# Controlador_de_velocidad_-_Placa_fuente_.net
KiCad netlist of a schematic drawn in Altium Designer
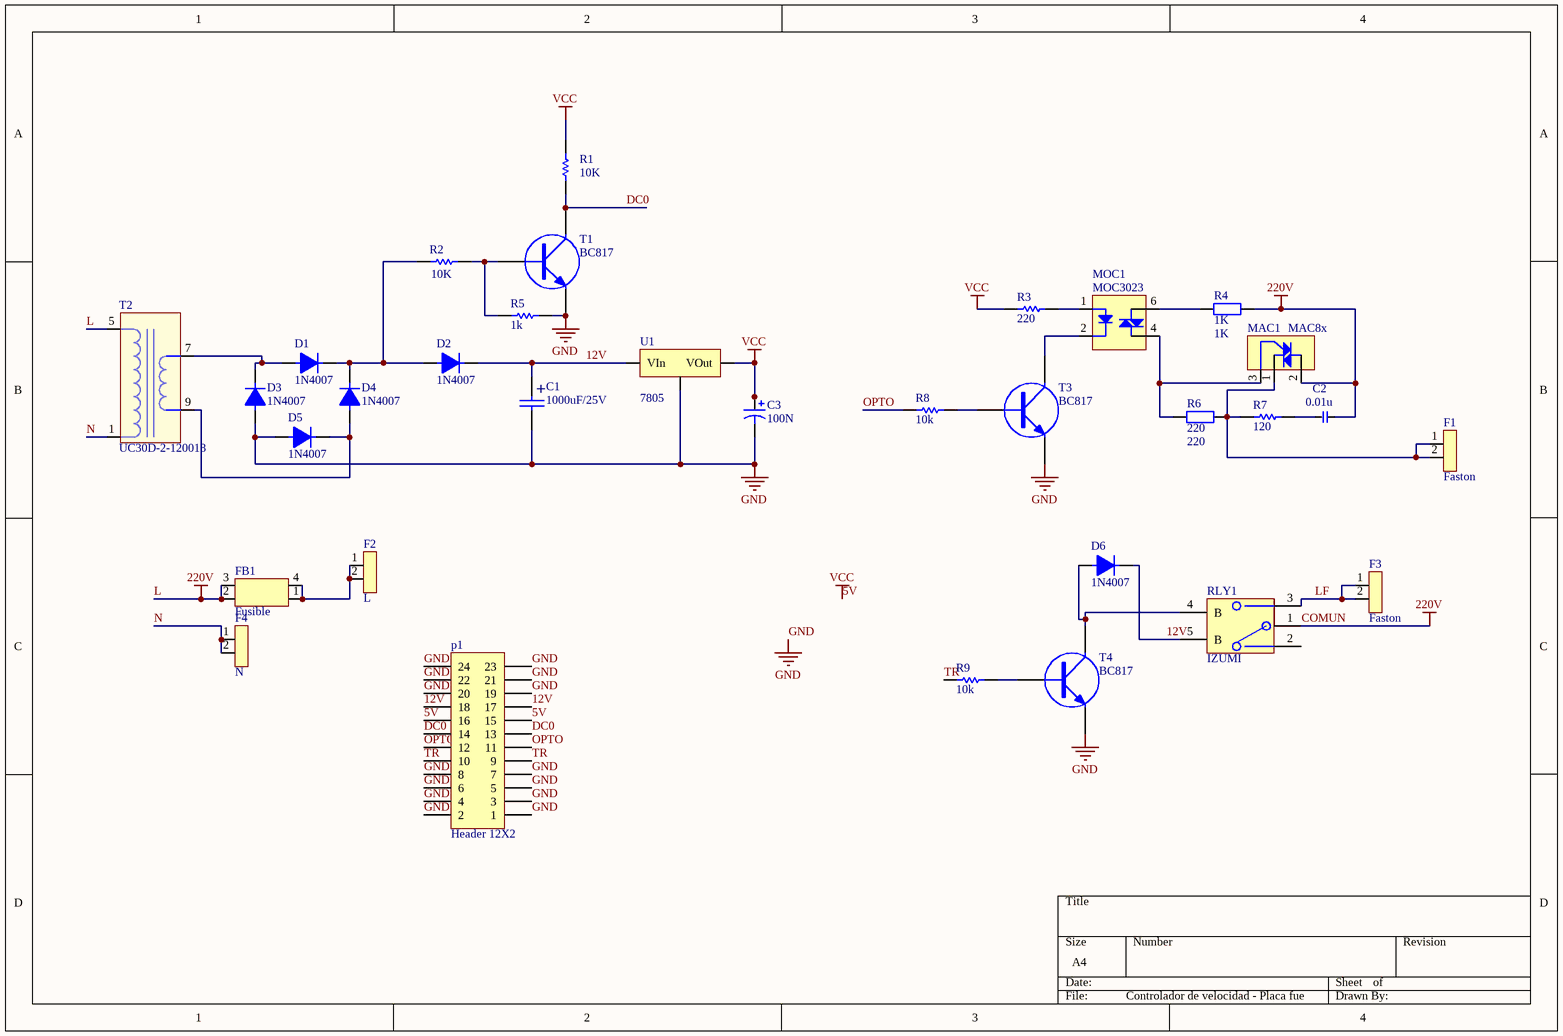
[diagram p0: Controlador de velocidad - Placa fuente v2.SchDoc]

(export (version "E")
  (design (tool "Eeschema 10.0.6"))
  (components
    (comp (ref "C1") (value "1000uF/25V") (footprint "CAP300RP") (libsource (lib "LIBPIOIX") (part "CAPPOL")))
    (comp (ref "C2")
      (value "0.01u")
      (footprint "AXIAL-0.4")
      (libsource (lib "Integrated_Lib_1") (part "CAP_MINI_NPOL"))
    )
    (comp (ref "C3")
      (value "100N")
      (footprint "C0805")
      (description "Polarized Capacitor (Surface Mount)")
      (fields (field (name "PUBLISHER") "Altium Limited"))
      (libsource (lib "Miscellaneous Devices") (part "Cap Pol3"))
    )
    (comp (ref "D1") (value "1N4007") (footprint "DO41") (libsource (lib "LIBPIOIX 0314A") (part "DIODO")))
    (comp (ref "D2") (value "1N4007") (footprint "DO41") (libsource (lib "LIBPIOIX 0314A") (part "DIODO")))
    (comp (ref "D3") (value "1N4007") (footprint "DO41") (libsource (lib "LIBPIOIX 0314A") (part "DIODO")))
    (comp (ref "D4") (value "1N4007") (footprint "DO41") (libsource (lib "LIBPIOIX 0314A") (part "DIODO")))
    (comp (ref "D5") (value "1N4007") (footprint "DO41") (libsource (lib "LIBPIOIX 0314A") (part "DIODO")))
    (comp (ref "D6") (value "1N4007") (footprint "DO41") (libsource (lib "LIBPIOIX 0314A") (part "DIODO")))
    (comp (ref "F1")
      (value "Faston")
      (footprint "Faston_V")
      (libsource (lib "Integrated_Library1") (part "FastonX1"))
    )
    (comp (ref "F2")
      (value "L")
      (footprint "Faston_V")
      (libsource (lib "Integrated_Library1") (part "FastonX1"))
    )
    (comp (ref "F3")
      (value "Faston")
      (footprint "Faston_V")
      (libsource (lib "Integrated_Library1") (part "FastonX1"))
    )
    (comp (ref "F4")
      (value "N")
      (footprint "Faston_V")
      (libsource (lib "Integrated_Library1") (part "FastonX1"))
    )
    (comp (ref "FB1")
      (value "Fusible")
      (footprint "Porta_fuse_2")
      (libsource (lib "Integrated_Library1") (part "Porta_fuse_1"))
    )
    (comp (ref "MAC1")
      (value "MAC8x")
      (footprint "TO-220_vert")
      (libsource (lib "Integrated_Library1") (part "MAC8x"))
    )
    (comp (ref "MOC1")
      (value "MOC3023")
      (footprint "4N33")
      (libsource (lib "Integrated_Library1") (part "MOC3023"))
    )
    (comp (ref "p1")
      (value "Header 12X2")
      (footprint "HDR2X12")
      (description "Header, 12-Pin, Dual row")
      (fields (field (name "PUBLISHER") "Altium Limited"))
      (libsource (lib "Miscellaneous Connectors") (part "Header 12X2"))
    )
    (comp (ref "R1") (value "10K") (footprint "0805") (libsource (lib "LIBPIOIX") (part "RES")))
    (comp (ref "R2") (value "10K") (footprint "0805") (libsource (lib "LIBPIOIX") (part "RES")))
    (comp (ref "R3") (value "220") (footprint "0805") (libsource (lib "LIBPIOIX") (part "RES")))
    (comp (ref "R4")
      (value "1K")
      (footprint "AXIAL-0.4")
      (description "Resistor")
      (fields (field (name "ALTIUM_VALUE") "1K") (field (name "PUBLISHER") "Altium Limited"))
      (libsource (lib "Miscellaneous Devices") (part "Res2"))
    )
    (comp (ref "R5") (value "1k") (footprint "0805") (libsource (lib "LIBPIOIX") (part "RES")))
    (comp (ref "R6")
      (value "220")
      (footprint "AXIAL-0.4")
      (description "Resistor")
      (fields (field (name "ALTIUM_VALUE") "220") (field (name "PUBLISHER") "Altium Limited"))
      (libsource (lib "Miscellaneous Devices") (part "Res2"))
    )
    (comp (ref "R7") (value "120") (footprint "RES400") (libsource (lib "LIBPIOIX") (part "RES")))
    (comp (ref "R8") (value "10k") (footprint "0805") (libsource (lib "LIBPIOIX") (part "RES")))
    (comp (ref "R9") (value "10k") (footprint "0805") (libsource (lib "LIBPIOIX") (part "RES")))
    (comp (ref "RLY1")
      (value "IZUMI")
      (footprint "Relay NT73-2")
      (libsource (lib "Integrated_Library_2") (part "RELE_SPSP"))
    )
    (comp (ref "T1")
      (value "BC817")
      (footprint "SOT23")
      (libsource (lib "LIBPIOIX 0314A") (part "TRANSISTOR NPN"))
    )
    (comp (ref "T2")
      (value "UC30D-2-120018")
      (footprint "Trafo_220_12_1")
      (libsource (lib "Integrated_Lib_1") (part "TRAFO_220_12_1"))
    )
    (comp (ref "T3")
      (value "BC817")
      (footprint "SOT23")
      (libsource (lib "LIBPIOIX 0314A") (part "TRANSISTOR NPN"))
    )
    (comp (ref "T4")
      (value "BC817")
      (footprint "SOT23")
      (libsource (lib "LIBPIOIX 0314A") (part "TRANSISTOR NPN"))
    )
    (comp (ref "U1")
      (value "7805")
      (footprint "TO-220 V")
      (description "REGULDOR POSITIVO")
      (libsource (lib "LIBPIOIX") (part "78XX"))
    )
  )
  (nets
    (net (code "1") (name "/12V") (class "Default")
      (node (ref "C1") (pin "1") (pinfunction "1_1") (pintype "passive"))
      (node (ref "D2") (pin "2") (pinfunction "2_2") (pintype "passive"))
      (node (ref "D6") (pin "2") (pinfunction "2_2") (pintype "passive"))
      (node (ref "RLY1") (pin "5") (pinfunction "B_5") (pintype "passive"))
      (node (ref "U1") (pin "1") (pinfunction "VIn_1") (pintype "passive"))
      (node (ref "p1") (pin "17") (pinfunction "17_17") (pintype "passive"))
      (node (ref "p1") (pin "18") (pinfunction "18_18") (pintype "passive"))
    )
    (net (code "2") (name "/DC0") (class "Default")
      (node (ref "R1") (pin "1") (pinfunction "1_1") (pintype "passive"))
      (node (ref "T1") (pin "2") (pinfunction "C_2") (pintype "passive"))
      (node (ref "p1") (pin "13") (pinfunction "13_13") (pintype "passive"))
      (node (ref "p1") (pin "14") (pinfunction "14_14") (pintype "passive"))
    )
    (net (code "3") (name "/LF") (class "Default")
      (node (ref "F3") (pin "1") (pintype "power_in"))
      (node (ref "F3") (pin "2") (pintype "power_in"))
      (node (ref "RLY1") (pin "3") (pinfunction "NA_3") (pintype "passive"))
    )
    (net (code "4") (name "/N") (class "Default")
      (node (ref "F4") (pin "1") (pintype "power_in"))
      (node (ref "F4") (pin "2") (pintype "power_in"))
      (node (ref "T2") (pin "1") (pinfunction "1_1") (pintype "passive"))
    )
    (net (code "5") (name "/OPTO") (class "Default")
      (node (ref "R8") (pin "1") (pinfunction "1_1") (pintype "passive"))
      (node (ref "p1") (pin "11") (pinfunction "11_11") (pintype "passive"))
      (node (ref "p1") (pin "12") (pinfunction "12_12") (pintype "passive"))
    )
    (net (code "6") (name "/TR") (class "Default")
      (node (ref "R9") (pin "1") (pinfunction "1_1") (pintype "passive"))
      (node (ref "p1") (pin "10") (pinfunction "10_10") (pintype "passive"))
      (node (ref "p1") (pin "9") (pinfunction "9_9") (pintype "passive"))
    )
    (net (code "7") (name "220V") (class "Default")
      (node (ref "C2") (pin "1") (pinfunction "1_1") (pintype "passive"))
      (node (ref "FB1") (pin "2") (pintype "power_in"))
      (node (ref "FB1") (pin "3") (pintype "power_in"))
      (node (ref "MAC1") (pin "2") (pinfunction "MT2_2") (pintype "passive"))
      (node (ref "R4") (pin "2") (pinfunction "2_2") (pintype "passive"))
      (node (ref "RLY1") (pin "1") (pinfunction "C_1") (pintype "passive"))
      (node (ref "T2") (pin "5") (pinfunction "5_5") (pintype "passive"))
    )
    (net (code "8") (name "GND") (class "Default")
      (node (ref "C1") (pin "2") (pinfunction "2_2") (pintype "passive"))
      (node (ref "C3") (pin "2") (pinfunction "2_2") (pintype "passive"))
      (node (ref "D3") (pin "1") (pinfunction "1_1") (pintype "passive"))
      (node (ref "D5") (pin "1") (pinfunction "1_1") (pintype "passive"))
      (node (ref "R5") (pin "2") (pinfunction "2_2") (pintype "passive"))
      (node (ref "T1") (pin "3") (pinfunction "E_3") (pintype "passive"))
      (node (ref "T3") (pin "3") (pinfunction "E_3") (pintype "passive"))
      (node (ref "T4") (pin "3") (pinfunction "E_3") (pintype "passive"))
      (node (ref "U1") (pin "2") (pinfunction "GND_2") (pintype "passive"))
      (node (ref "p1") (pin "1") (pinfunction "1_1") (pintype "passive"))
      (node (ref "p1") (pin "19") (pinfunction "19_19") (pintype "passive"))
      (node (ref "p1") (pin "2") (pinfunction "2_2") (pintype "passive"))
      (node (ref "p1") (pin "20") (pinfunction "20_20") (pintype "passive"))
      (node (ref "p1") (pin "21") (pinfunction "21_21") (pintype "passive"))
      (node (ref "p1") (pin "22") (pinfunction "22_22") (pintype "passive"))
      (node (ref "p1") (pin "23") (pinfunction "23_23") (pintype "passive"))
      (node (ref "p1") (pin "24") (pinfunction "24_24") (pintype "passive"))
      (node (ref "p1") (pin "3") (pinfunction "3_3") (pintype "passive"))
      (node (ref "p1") (pin "4") (pinfunction "4_4") (pintype "passive"))
      (node (ref "p1") (pin "5") (pinfunction "5_5") (pintype "passive"))
      (node (ref "p1") (pin "6") (pinfunction "6_6") (pintype "passive"))
      (node (ref "p1") (pin "7") (pinfunction "7_7") (pintype "passive"))
      (node (ref "p1") (pin "8") (pinfunction "8_8") (pintype "passive"))
    )
    (net (code "9") (name "Net-(C2-Pad2)") (class "Default")
      (node (ref "C2") (pin "2") (pinfunction "2_2") (pintype "passive"))
      (node (ref "R7") (pin "1") (pinfunction "1_1") (pintype "passive"))
    )
    (net (code "10") (name "Net-(D1-Pad1)") (class "Default")
      (node (ref "D1") (pin "1") (pinfunction "1_1") (pintype "passive"))
      (node (ref "D3") (pin "2") (pinfunction "2_2") (pintype "passive"))
      (node (ref "T2") (pin "7") (pinfunction "7_7") (pintype "passive"))
    )
    (net (code "11") (name "Net-(D1-Pad2)") (class "Default")
      (node (ref "D1") (pin "2") (pinfunction "2_2") (pintype "passive"))
      (node (ref "D2") (pin "1") (pinfunction "1_1") (pintype "passive"))
      (node (ref "D4") (pin "2") (pinfunction "2_2") (pintype "passive"))
      (node (ref "R2") (pin "1") (pinfunction "1_1") (pintype "passive"))
    )
    (net (code "12") (name "Net-(D4-Pad1)") (class "Default")
      (node (ref "D4") (pin "1") (pinfunction "1_1") (pintype "passive"))
      (node (ref "D5") (pin "2") (pinfunction "2_2") (pintype "passive"))
      (node (ref "T2") (pin "9") (pinfunction "9_9") (pintype "passive"))
    )
    (net (code "13") (name "Net-(F2-Pad1)") (class "Default")
      (node (ref "F2") (pin "1") (pintype "power_in"))
      (node (ref "F2") (pin "2") (pintype "power_in"))
      (node (ref "FB1") (pin "1") (pintype "power_in"))
      (node (ref "FB1") (pin "4") (pintype "power_in"))
    )
    (net (code "14") (name "Net-(MAC1-G)") (class "Default")
      (node (ref "MAC1") (pin "3") (pinfunction "G_3") (pintype "passive"))
      (node (ref "MOC1") (pin "4") (pintype "passive"))
      (node (ref "R6") (pin "1") (pinfunction "1_1") (pintype "passive"))
    )
    (net (code "15") (name "Net-(MAC1-MT1)") (class "Default")
      (node (ref "F1") (pin "1") (pintype "power_in"))
      (node (ref "F1") (pin "2") (pintype "power_in"))
      (node (ref "MAC1") (pin "1") (pinfunction "MT1_1") (pintype "passive"))
      (node (ref "R6") (pin "2") (pinfunction "2_2") (pintype "passive"))
      (node (ref "R7") (pin "2") (pinfunction "2_2") (pintype "passive"))
    )
    (net (code "16") (name "Net-(MOC1-Pad1)") (class "Default")
      (node (ref "MOC1") (pin "1") (pintype "passive"))
      (node (ref "R3") (pin "2") (pinfunction "2_2") (pintype "passive"))
    )
    (net (code "17") (name "Net-(MOC1-Pad6)") (class "Default")
      (node (ref "MOC1") (pin "6") (pintype "passive"))
      (node (ref "R4") (pin "1") (pinfunction "1_1") (pintype "passive"))
    )
    (net (code "18") (name "Net-(T1-B)") (class "Default")
      (node (ref "R2") (pin "2") (pinfunction "2_2") (pintype "passive"))
      (node (ref "R5") (pin "1") (pinfunction "1_1") (pintype "passive"))
      (node (ref "T1") (pin "1") (pinfunction "B_1") (pintype "passive"))
    )
    (net (code "19") (name "Net-(T3-B)") (class "Default")
      (node (ref "R8") (pin "2") (pinfunction "2_2") (pintype "passive"))
      (node (ref "T3") (pin "1") (pinfunction "B_1") (pintype "passive"))
    )
    (net (code "20") (name "Net-(T3-C)") (class "Default")
      (node (ref "MOC1") (pin "2") (pintype "passive"))
      (node (ref "T3") (pin "2") (pinfunction "C_2") (pintype "passive"))
    )
    (net (code "21") (name "Net-(T4-B)") (class "Default")
      (node (ref "R9") (pin "2") (pinfunction "2_2") (pintype "passive"))
      (node (ref "T4") (pin "1") (pinfunction "B_1") (pintype "passive"))
    )
    (net (code "22") (name "Net-(T4-C)") (class "Default")
      (node (ref "D6") (pin "1") (pinfunction "1_1") (pintype "passive"))
      (node (ref "RLY1") (pin "4") (pinfunction "B_4") (pintype "passive"))
      (node (ref "T4") (pin "2") (pinfunction "C_2") (pintype "passive"))
    )
    (net (code "23") (name "VCC") (class "Default")
      (node (ref "C3") (pin "1") (pinfunction "1_1") (pintype "passive"))
      (node (ref "R1") (pin "2") (pinfunction "2_2") (pintype "passive"))
      (node (ref "R3") (pin "1") (pinfunction "1_1") (pintype "passive"))
      (node (ref "U1") (pin "3") (pinfunction "VOut_3") (pintype "passive"))
      (node (ref "p1") (pin "15") (pinfunction "15_15") (pintype "passive"))
      (node (ref "p1") (pin "16") (pinfunction "16_16") (pintype "passive"))
    )
    (net (code "24") (name "unconnected-(RLY1-NC-Pad2)") (class "Default")
      (node (ref "RLY1") (pin "2") (pinfunction "NC_2") (pintype "passive"))
    )
  )
)
